# Solar.net
KiCad netlist of a schematic drawn in Altium Designer
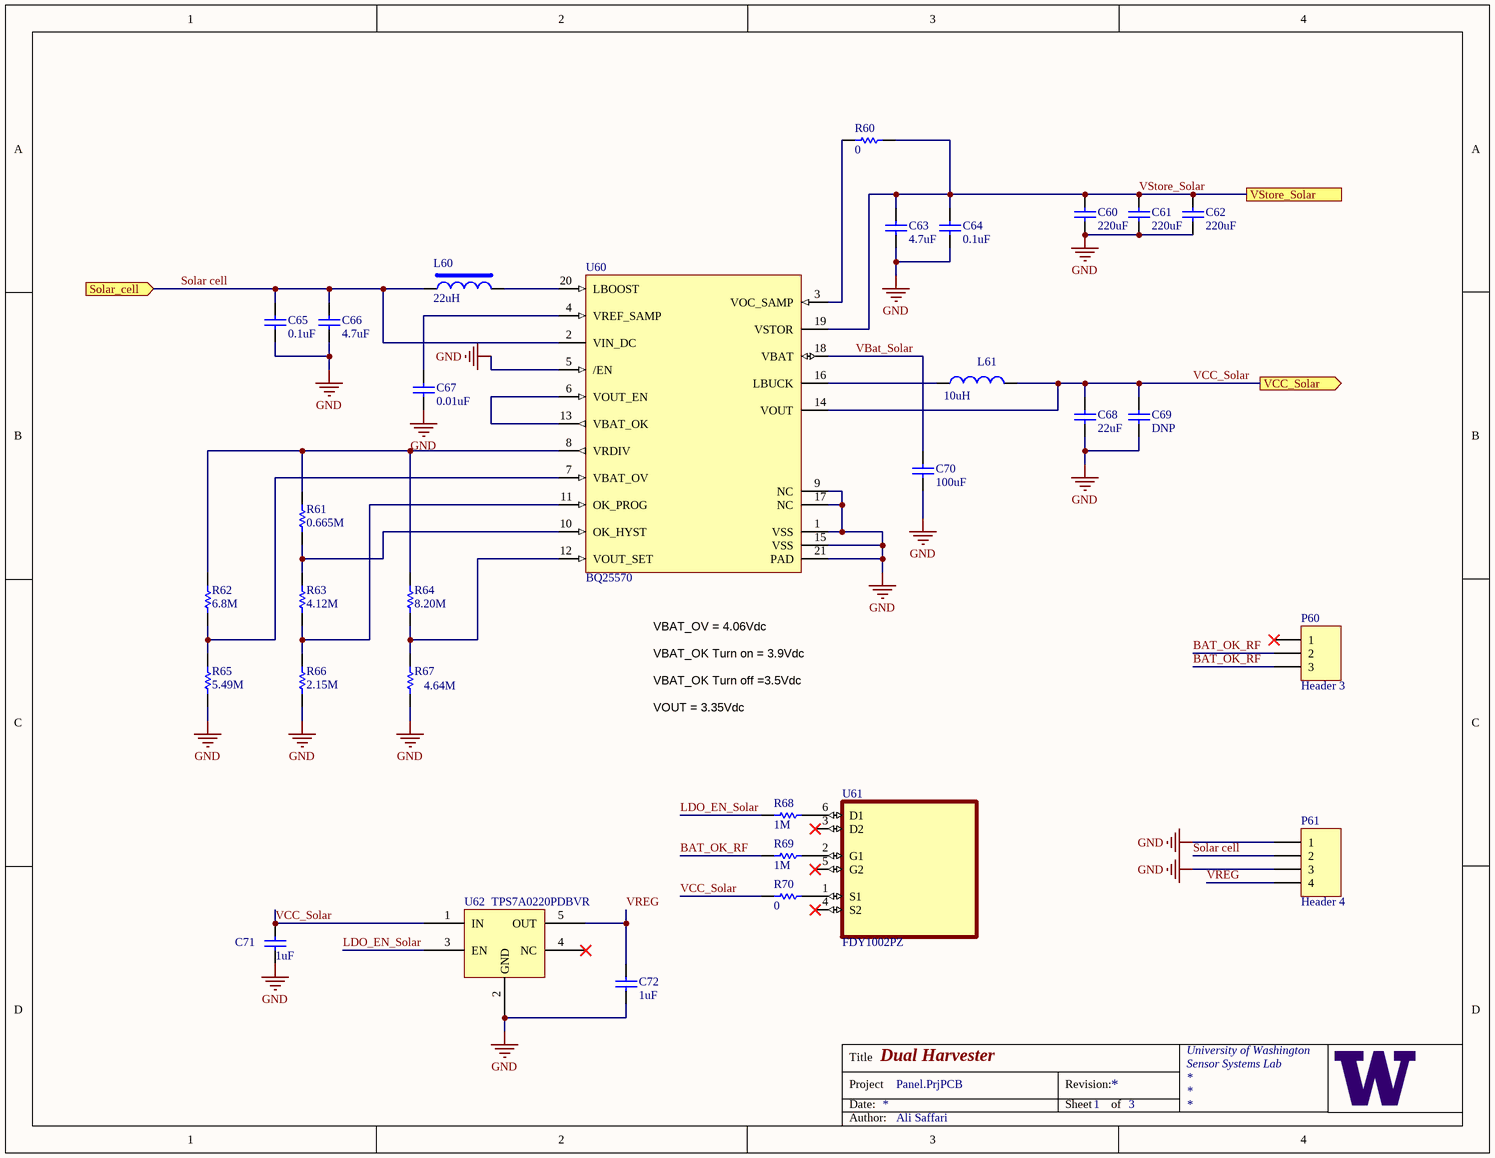
[diagram p0: Solar.SchDoc]

(export (version "E")
  (design (tool "Eeschema 10.0.6"))
  (components
    (comp (ref "C60")
      (value "220uF")
      (footprint "1206")
      (description "Ceramic Capacitor (Surface Mount)")
      (fields
        (field (name "DIGI-KEY PART NUMBER") "490-13970-1-ND")
        (field (name "MANUFACTURER") "Murata Electronics")
      )
      (libsource (lib "WISP_AD10") (part "Cap"))
    )
    (comp (ref "C61")
      (value "220uF")
      (footprint "1206")
      (description "Ceramic Capacitor (Surface Mount)")
      (fields
        (field (name "DIGI-KEY PART NUMBER") "490-13970-1-ND")
        (field (name "MANUFACTURER") "Murata Electronics")
      )
      (libsource (lib "WISP_AD10") (part "Cap"))
    )
    (comp (ref "C62")
      (value "220uF")
      (footprint "1206")
      (description "Ceramic Capacitor (Surface Mount)")
      (fields
        (field (name "DIGI-KEY PART NUMBER") "490-13970-1-ND")
        (field (name "MANUFACTURER") "Murata Electronics")
      )
      (libsource (lib "WISP_AD10") (part "Cap"))
    )
    (comp (ref "C63")
      (value "4.7uF")
      (footprint "0402")
      (description "Ceramic Capacitor (Surface Mount)")
      (fields
        (field (name "DIGI-KEY PART NUMBER") "490-14306-1-ND")
        (field (name "MANUFACTURER") "Murata Electronics")
      )
      (libsource (lib "WISP_AD10") (part "Cap"))
    )
    (comp (ref "C64")
      (value "0.1uF")
      (footprint "0402")
      (description "Ceramic Capacitor (Surface Mount)")
      (fields
        (field (name "DIGI-KEY PART NUMBER") "490-4759-1-ND")
        (field (name "MANUFACTURER") "Murata Electronics North America")
      )
      (libsource (lib "WISP_AD10") (part "Cap"))
    )
    (comp (ref "C65")
      (value "0.1uF")
      (footprint "0402")
      (description "Ceramic Capacitor (Surface Mount)")
      (fields
        (field (name "DIGI-KEY PART NUMBER") "490-4759-1-ND")
        (field (name "MANUFACTURER") "Murata Electronics North America")
      )
      (libsource (lib "WISP_AD10") (part "Cap"))
    )
    (comp (ref "C66")
      (value "4.7uF")
      (footprint "0402")
      (description "Ceramic Capacitor (Surface Mount)")
      (fields
        (field (name "DIGI-KEY PART NUMBER") "490-14306-1-ND")
        (field (name "MANUFACTURER") "Murata Electronics")
      )
      (libsource (lib "WISP_AD10") (part "Cap"))
    )
    (comp (ref "C67")
      (value "0.01uF")
      (footprint "0402")
      (description "Ceramic Capacitor (Surface Mount)")
      (fields
        (field (name "DIGI-KEY PART NUMBER") "490-14306-1-ND")
        (field (name "MANUFACTURER") "Murata Electronics")
      )
      (libsource (lib "WISP_AD10") (part "Cap"))
    )
    (comp (ref "C68")
      (value "22uF")
      (footprint "0402")
      (description "Ceramic Capacitor (Surface Mount)")
      (fields
        (field (name "DIGI-KEY PART NUMBER") "490-10476-1-ND")
        (field (name "MANUFACTURER") "Murata Electronics")
      )
      (libsource (lib "WISP_AD10") (part "Cap"))
    )
    (comp (ref "C69")
      (value "DNP")
      (footprint "0402")
      (description "Ceramic Capacitor (Surface Mount)")
      (fields
        (field (name "DIGI-KEY PART NUMBER") "490-10476-1-ND")
        (field (name "MANUFACTURER") "Murata Electronics")
      )
      (libsource (lib "WISP_AD10") (part "Cap"))
    )
    (comp (ref "C70")
      (value "100uF")
      (footprint "0805")
      (description "Ceramic Capacitor (Surface Mount)")
      (fields
        (field (name "DIGI-KEY PART NUMBER") "490-13981-1-ND")
        (field (name "MANUFACTURER") "Murata Electronics")
      )
      (libsource (lib "WISP_AD10") (part "Cap"))
    )
    (comp (ref "C71")
      (value "1uF")
      (footprint "0402")
      (description "Ceramic Capacitor (Surface Mount)")
      (fields (field (name "MANUFACTURER") "Generic Ceramic Chip Cap (TBD)") (field (name "Comment") "Cap"))
      (libsource (lib "WISP_AD10") (part "Cap"))
    )
    (comp (ref "C72")
      (value "1uF")
      (footprint "0402")
      (description "Ceramic Capacitor (Surface Mount)")
      (fields (field (name "MANUFACTURER") "Generic Ceramic Chip Cap (TBD)") (field (name "Comment") "Cap"))
      (libsource (lib "WISP_AD10") (part "Cap"))
    )
    (comp (ref "L60")
      (value "22uH")
      (footprint "LPS4018")
      (description "Inductor (Surface Mount)")
      (fields
        (field (name "MANUFACTURER") "Coil Craft")
        (field (name "MANUFACTURER PART NUMBER") "LPS4018-223MRB")
      )
      (libsource (lib "WISP_AD10") (part "Ind_LPS4018"))
    )
    (comp (ref "L61")
      (value "10uH")
      (footprint "IND1008")
      (description "Inductor (Surface Mount)")
      (fields
        (field (name "DIGI-KEY PART NUMBER") "490-10563-1-ND")
        (field (name "MANUFACTURER") "Murata Electronics")
      )
      (libsource (lib "WISP_AD10") (part "Ind"))
    )
    (comp (ref "P60")
      (value "Header 3")
      (footprint "HDR1X3")
      (description "Header, 3-Pin")
      (fields (field (name "PUBLISHER") "Altium Limited"))
      (libsource (lib "Miscellaneous Connectors") (part "Header 3"))
    )
    (comp (ref "P61")
      (value "Header 4")
      (footprint "HDR1X4")
      (description "Header, 4-Pin")
      (fields (field (name "PUBLISHER") "Altium Limited"))
      (libsource (lib "Miscellaneous Connectors") (part "Header 4"))
    )
    (comp (ref "R60")
      (value "0")
      (footprint "0402")
      (description "Chip Resistor (Surface Mount)")
      (fields
        (field (name "MANUFACTURER") "Yageo")
        (field (name "MANUFACTURER PART NUMBER") "RC0402JR-070RL")
      )
      (libsource (lib "WISP_AD10") (part "Res"))
    )
    (comp (ref "R61")
      (value "0.665M")
      (footprint "0402")
      (description "Chip Resistor (Surface Mount)")
      (fields
        (field (name "MANUFACTURER") "Yageo")
        (field (name "MANUFACTURER PART NUMBER") "RC0402FR-073M3L")
      )
      (libsource (lib "WISP_AD10") (part "Res"))
    )
    (comp (ref "R62")
      (value "6.8M")
      (footprint "0402")
      (description "Chip Resistor (Surface Mount)")
      (fields
        (field (name "MANUFACTURER") "Vishay Dale")
        (field (name "MANUFACTURER PART NUMBER") "CRCW04026M80JNED")
      )
      (libsource (lib "WISP_AD10") (part "Res"))
    )
    (comp (ref "R63")
      (value "4.12M")
      (footprint "0402")
      (description "Chip Resistor (Surface Mount)")
      (fields
        (field (name "MANUFACTURER") "Vishay Dale")
        (field (name "MANUFACTURER PART NUMBER") "CRCW04025M49FKED")
      )
      (libsource (lib "WISP_AD10") (part "Res"))
    )
    (comp (ref "R64")
      (value "8.20M")
      (footprint "0402")
      (description "Chip Resistor (Surface Mount)")
      (fields
        (field (name "MANUFACTURER") "Vishay Dale")
        (field (name "MANUFACTURER PART NUMBER") "CRCW04026M80JNED")
      )
      (libsource (lib "WISP_AD10") (part "Res"))
    )
    (comp (ref "R65")
      (value "5.49M")
      (footprint "0402")
      (description "Chip Resistor (Surface Mount)")
      (fields
        (field (name "MANUFACTURER") "Vishay Dale")
        (field (name "MANUFACTURER PART NUMBER") "CRCW04025M49FKED")
      )
      (libsource (lib "WISP_AD10") (part "Res"))
    )
    (comp (ref "R66")
      (value "2.15M")
      (footprint "0402")
      (description "Chip Resistor (Surface Mount)")
      (fields
        (field (name "MANUFACTURER") "Vishay Dale")
        (field (name "MANUFACTURER PART NUMBER") "CRCW04024M22FKED")
      )
      (libsource (lib "WISP_AD10") (part "Res"))
    )
    (comp (ref "R67")
      (value "4.64M")
      (footprint "0402")
      (description "Chip Resistor (Surface Mount)")
      (fields
        (field (name "MANUFACTURER") "Vishay Dale")
        (field (name "MANUFACTURER PART NUMBER") "CRCW04025M49FKED")
      )
      (libsource (lib "WISP_AD10") (part "Res"))
    )
    (comp (ref "R68")
      (value "1M")
      (footprint "0402")
      (description "Chip Resistor (Surface Mount)")
      (fields
        (field (name "MANUFACTURER") "Yageo")
        (field (name "MANUFACTURER PART NUMBER") "RC0402JR-070RL")
      )
      (libsource (lib "WISP_AD10") (part "Res"))
    )
    (comp (ref "R69")
      (value "1M")
      (footprint "0402")
      (description "Chip Resistor (Surface Mount)")
      (fields
        (field (name "MANUFACTURER") "Yageo")
        (field (name "MANUFACTURER PART NUMBER") "RC0402JR-070RL")
      )
      (libsource (lib "WISP_AD10") (part "Res"))
    )
    (comp (ref "R70")
      (value "0")
      (footprint "0402")
      (description "Chip Resistor (Surface Mount)")
      (fields
        (field (name "MANUFACTURER") "Yageo")
        (field (name "MANUFACTURER PART NUMBER") "RC0402JR-070RL")
      )
      (libsource (lib "WISP_AD10") (part "Res"))
    )
    (comp (ref "U60")
      (value "BQ25570")
      (footprint "BQ25570")
      (description "nano power boost charger and buck converter\r\nfor energy harvester powered applications")
      (fields
        (field (name "DIGI-KEY PART NUMBER") "296-37014-1-ND")
        (field (name "MANUFACTURER") "Texas Instruments")
      )
      (libsource (lib "BLE") (part "BQ25570"))
    )
    (comp (ref "U61")
      (value "FDY1002PZ")
      (footprint "SOT50P160X60-6N")
      (description "Mosfet Array 2 P-Channel (Dual) 20V 830mA 446mW Surface Mount SOT-563F")
      (fields (field (name "MF") "ON Semiconductor"))
      (libsource (lib "FDY1002PZ") (part "FDY1002PZ"))
    )
    (comp (ref "U62")
      (value "TPS7A0220PDBVR")
      (footprint "SOT23-5")
      (description "IC REG LINEAR 2V 200MA SOT23-5")
      (libsource (lib "WISP_AD10") (part "TPS7A0218PDBVR"))
    )
  )
  (nets
    (net (code "1") (name "/BAT_OK_RF") (class "Default")
      (node (ref "P60") (pin "2") (pinfunction "2_2") (pintype "passive"))
      (node (ref "P60") (pin "3") (pinfunction "3_3") (pintype "passive"))
      (node (ref "R69") (pin "1") (pinfunction "1_1") (pintype "passive"))
    )
    (net (code "2") (name "/LDO_EN_Solar") (class "Default")
      (node (ref "R68") (pin "1") (pinfunction "1_1") (pintype "passive"))
      (node (ref "U62") (pin "3") (pinfunction "EN_3") (pintype "passive"))
    )
    (net (code "3") (name "/Solar cell") (class "Default")
      (node (ref "C65") (pin "2") (pinfunction "2_2") (pintype "passive"))
      (node (ref "C66") (pin "2") (pinfunction "2_2") (pintype "passive"))
      (node (ref "L60") (pin "1") (pinfunction "1_1") (pintype "passive"))
      (node (ref "P61") (pin "2") (pinfunction "2_2") (pintype "passive"))
      (node (ref "U60") (pin "2") (pinfunction "VIN_DC_2") (pintype "passive"))
    )
    (net (code "4") (name "/VBat_Solar") (class "Default")
      (node (ref "C70") (pin "2") (pinfunction "2_2") (pintype "passive"))
      (node (ref "U60") (pin "18") (pinfunction "VBAT_18") (pintype "bidirectional"))
    )
    (net (code "5") (name "/VCC_Solar") (class "Default")
      (node (ref "C68") (pin "2") (pinfunction "2_2") (pintype "passive"))
      (node (ref "C69") (pin "2") (pinfunction "2_2") (pintype "passive"))
      (node (ref "C71") (pin "2") (pinfunction "2_2") (pintype "passive"))
      (node (ref "L61") (pin "2") (pinfunction "2_2") (pintype "passive"))
      (node (ref "R70") (pin "1") (pinfunction "1_1") (pintype "passive"))
      (node (ref "U60") (pin "14") (pinfunction "VOUT_14") (pintype "passive"))
      (node (ref "U62") (pin "1") (pinfunction "IN_1") (pintype "passive"))
    )
    (net (code "6") (name "/VREG") (class "Default")
      (node (ref "C72") (pin "2") (pinfunction "2_2") (pintype "passive"))
      (node (ref "P61") (pin "4") (pinfunction "4_4") (pintype "passive"))
      (node (ref "U62") (pin "5") (pinfunction "OUT_5") (pintype "passive"))
    )
    (net (code "7") (name "/VStore_Solar") (class "Default")
      (node (ref "C60") (pin "2") (pinfunction "2_2") (pintype "passive"))
      (node (ref "C61") (pin "2") (pinfunction "2_2") (pintype "passive"))
      (node (ref "C62") (pin "2") (pinfunction "2_2") (pintype "passive"))
      (node (ref "C63") (pin "2") (pinfunction "2_2") (pintype "passive"))
      (node (ref "C64") (pin "2") (pinfunction "2_2") (pintype "passive"))
      (node (ref "R60") (pin "2") (pinfunction "2_2") (pintype "passive"))
      (node (ref "U60") (pin "19") (pinfunction "VSTOR_19") (pintype "passive"))
    )
    (net (code "8") (name "GND") (class "Default")
      (node (ref "C60") (pin "1") (pinfunction "1_1") (pintype "passive"))
      (node (ref "C61") (pin "1") (pinfunction "1_1") (pintype "passive"))
      (node (ref "C62") (pin "1") (pinfunction "1_1") (pintype "passive"))
      (node (ref "C63") (pin "1") (pinfunction "1_1") (pintype "passive"))
      (node (ref "C64") (pin "1") (pinfunction "1_1") (pintype "passive"))
      (node (ref "C65") (pin "1") (pinfunction "1_1") (pintype "passive"))
      (node (ref "C66") (pin "1") (pinfunction "1_1") (pintype "passive"))
      (node (ref "C67") (pin "1") (pinfunction "1_1") (pintype "passive"))
      (node (ref "C68") (pin "1") (pinfunction "1_1") (pintype "passive"))
      (node (ref "C69") (pin "1") (pinfunction "1_1") (pintype "passive"))
      (node (ref "C70") (pin "1") (pinfunction "1_1") (pintype "passive"))
      (node (ref "C71") (pin "1") (pinfunction "1_1") (pintype "passive"))
      (node (ref "C72") (pin "1") (pinfunction "1_1") (pintype "passive"))
      (node (ref "P61") (pin "1") (pinfunction "1_1") (pintype "passive"))
      (node (ref "P61") (pin "3") (pinfunction "3_3") (pintype "passive"))
      (node (ref "R65") (pin "2") (pinfunction "2_2") (pintype "passive"))
      (node (ref "R66") (pin "2") (pinfunction "2_2") (pintype "passive"))
      (node (ref "R67") (pin "2") (pinfunction "2_2") (pintype "passive"))
      (node (ref "U60") (pin "1") (pinfunction "VSS_1") (pintype "passive"))
      (node (ref "U60") (pin "15") (pinfunction "VSS_15") (pintype "passive"))
      (node (ref "U60") (pin "17") (pinfunction "NC_17") (pintype "passive"))
      (node (ref "U60") (pin "21") (pinfunction "PAD_21") (pintype "passive"))
      (node (ref "U60") (pin "5") (pinfunction "/EN_5") (pintype "input"))
      (node (ref "U60") (pin "9") (pinfunction "NC_9") (pintype "passive"))
      (node (ref "U62") (pin "2") (pinfunction "GND_2") (pintype "passive"))
    )
    (net (code "9") (name "Net-(U60-LBOOST)") (class "Default")
      (node (ref "L60") (pin "2") (pinfunction "2_2") (pintype "passive"))
      (node (ref "U60") (pin "20") (pinfunction "LBOOST_20") (pintype "input"))
    )
    (net (code "10") (name "Net-(U60-LBUCK)") (class "Default")
      (node (ref "L61") (pin "1") (pinfunction "1_1") (pintype "passive"))
      (node (ref "U60") (pin "16") (pinfunction "LBUCK_16") (pintype "passive"))
    )
    (net (code "11") (name "Net-(U60-OK_HYST)") (class "Default")
      (node (ref "R61") (pin "2") (pinfunction "2_2") (pintype "passive"))
      (node (ref "R63") (pin "1") (pinfunction "1_1") (pintype "passive"))
      (node (ref "U60") (pin "10") (pinfunction "OK_HYST_10") (pintype "input"))
    )
    (net (code "12") (name "Net-(U60-OK_PROG)") (class "Default")
      (node (ref "R63") (pin "2") (pinfunction "2_2") (pintype "passive"))
      (node (ref "R66") (pin "1") (pinfunction "1_1") (pintype "passive"))
      (node (ref "U60") (pin "11") (pinfunction "OK_PROG_11") (pintype "input"))
    )
    (net (code "13") (name "Net-(U60-VBAT_OK)") (class "Default")
      (node (ref "U60") (pin "13") (pinfunction "VBAT_OK_13") (pintype "output"))
      (node (ref "U60") (pin "6") (pinfunction "VOUT_EN_6") (pintype "input"))
    )
    (net (code "14") (name "Net-(U60-VBAT_OV)") (class "Default")
      (node (ref "R62") (pin "2") (pinfunction "2_2") (pintype "passive"))
      (node (ref "R65") (pin "1") (pinfunction "1_1") (pintype "passive"))
      (node (ref "U60") (pin "7") (pinfunction "VBAT_OV_7") (pintype "input"))
    )
    (net (code "15") (name "Net-(U60-VOC_SAMP)") (class "Default")
      (node (ref "R60") (pin "1") (pinfunction "1_1") (pintype "passive"))
      (node (ref "U60") (pin "3") (pinfunction "VOC_SAMP_3") (pintype "input"))
    )
    (net (code "16") (name "Net-(U60-VOUT_SET)") (class "Default")
      (node (ref "R64") (pin "2") (pinfunction "2_2") (pintype "passive"))
      (node (ref "R67") (pin "1") (pinfunction "1_1") (pintype "passive"))
      (node (ref "U60") (pin "12") (pinfunction "VOUT_SET_12") (pintype "input"))
    )
    (net (code "17") (name "Net-(U60-VRDIV)") (class "Default")
      (node (ref "R61") (pin "1") (pinfunction "1_1") (pintype "passive"))
      (node (ref "R62") (pin "1") (pinfunction "1_1") (pintype "passive"))
      (node (ref "R64") (pin "1") (pinfunction "1_1") (pintype "passive"))
      (node (ref "U60") (pin "8") (pinfunction "VRDIV_8") (pintype "output"))
    )
    (net (code "18") (name "Net-(U60-VREF_SAMP)") (class "Default")
      (node (ref "C67") (pin "2") (pinfunction "2_2") (pintype "passive"))
      (node (ref "U60") (pin "4") (pinfunction "VREF_SAMP_4") (pintype "input"))
    )
    (net (code "19") (name "Net-(U61-D1)") (class "Default")
      (node (ref "R68") (pin "2") (pinfunction "2_2") (pintype "passive"))
      (node (ref "U61") (pin "6") (pinfunction "D1_6") (pintype "bidirectional"))
    )
    (net (code "20") (name "Net-(U61-G1)") (class "Default")
      (node (ref "R69") (pin "2") (pinfunction "2_2") (pintype "passive"))
      (node (ref "U61") (pin "2") (pinfunction "G1_2") (pintype "bidirectional"))
    )
    (net (code "21") (name "Net-(U61-S1)") (class "Default")
      (node (ref "R70") (pin "2") (pinfunction "2_2") (pintype "passive"))
      (node (ref "U61") (pin "1") (pinfunction "S1_1") (pintype "bidirectional"))
    )
    (net (code "22") (name "unconnected-(P60-Pad1)") (class "Default")
      (node (ref "P60") (pin "1") (pinfunction "1_1") (pintype "passive+no_connect"))
    )
    (net (code "23") (name "unconnected-(U61-D2-Pad3)") (class "Default")
      (node (ref "U61") (pin "3") (pinfunction "D2_3") (pintype "bidirectional+no_connect"))
    )
    (net (code "24") (name "unconnected-(U61-G2-Pad5)") (class "Default")
      (node (ref "U61") (pin "5") (pinfunction "G2_5") (pintype "bidirectional+no_connect"))
    )
    (net (code "25") (name "unconnected-(U61-S2-Pad4)") (class "Default")
      (node (ref "U61") (pin "4") (pinfunction "S2_4") (pintype "bidirectional+no_connect"))
    )
    (net (code "26") (name "unconnected-(U62-NC-Pad4)") (class "Default")
      (node (ref "U62") (pin "4") (pinfunction "NC_4") (pintype "passive+no_connect"))
    )
  )
)
